# KCNFEQ_V0_1.net
KiCad netlist of a schematic drawn in Altium Designer
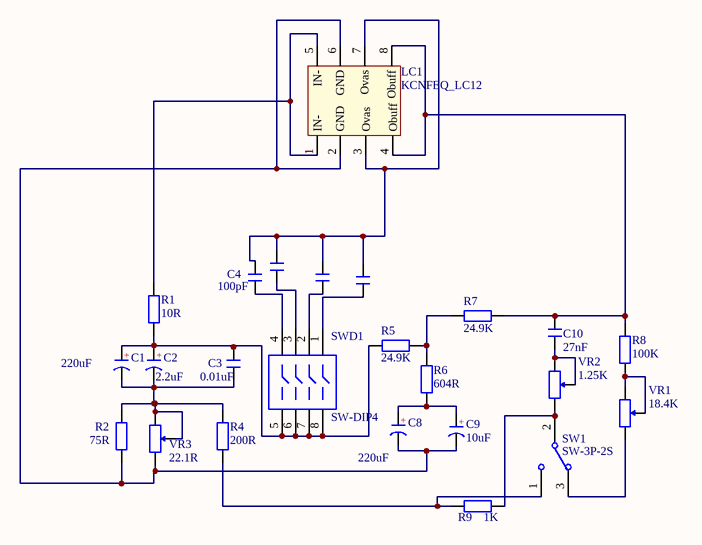
[diagram p0: KCNFEQ_V0.1.SchDoc]

(export (version "E")
  (design (tool "Eeschema 10.0.6"))
  (components
    (comp (ref "C1")
      (value "220uF")
      (footprint "CAP 5.0*10*12.5")
      (description "直插电解电容")
      (fields (field (name "版权归属") "源创客"))
      (libsource (lib "电阻-电容-电感") (part "C-CAP"))
    )
    (comp (ref "C2")
      (value "2.2uF")
      (footprint "CAP 5.0*10*12.5")
      (description "直插电解电容")
      (fields (field (name "版权归属") "源创客"))
      (libsource (lib "电阻-电容-电感") (part "C-CAP"))
    )
    (comp (ref "C3")
      (value "0.01uF")
      (footprint "CBB 6.3*6.3*5")
      (description "CBB电容")
      (fields (field (name "版权归属") "源创客"))
      (libsource (lib "电阻-电容-电感") (part "C-CBB"))
    )
    (comp (ref "C4")
      (value "100pF")
      (footprint "CBB 6.3*6.3*5")
      (description "CBB电容")
      (fields (field (name "版权归属") "源创客"))
      (libsource (lib "电阻-电容-电感") (part "C-CBB"))
    )
    (comp (ref "C6")
      (value "100pF")
      (footprint "CBB 6.3*6.3*5")
      (description "CBB电容")
      (fields (field (name "版权归属") "源创客"))
      (libsource (lib "电阻-电容-电感") (part "C-CBB"))
    )
    (comp (ref "C7")
      (value "20pF")
      (footprint "CBB 6.3*6.3*5")
      (description "CBB电容")
      (fields (field (name "版权归属") "源创客"))
      (libsource (lib "电阻-电容-电感") (part "C-CBB"))
    )
    (comp (ref "C8")
      (value "220uF")
      (footprint "CAP 5.0*10*12.5")
      (description "直插电解电容")
      (fields (field (name "版权归属") "源创客"))
      (libsource (lib "电阻-电容-电感") (part "C-CAP"))
    )
    (comp (ref "C9")
      (value "10uF")
      (footprint "CAP 5.0*10*12.5")
      (description "直插电解电容")
      (fields (field (name "版权归属") "源创客"))
      (libsource (lib "电阻-电容-电感") (part "C-CAP"))
    )
    (comp (ref "C10")
      (value "27nF")
      (footprint "CBB 6.3*6.3*5")
      (description "CBB电容")
      (fields (field (name "版权归属") "源创客"))
      (libsource (lib "电阻-电容-电感") (part "C-CBB"))
    )
    (comp (ref "C18")
      (value "60pF")
      (footprint "CBB 6.3*6.3*5")
      (description "CBB电容")
      (fields (field (name "版权归属") "源创客"))
      (libsource (lib "电阻-电容-电感") (part "C-CBB"))
    )
    (comp (ref "LC1")
      (value "KCNFEQ_LC12")
      (footprint "LC12-3.81")
      (description "King Cello Negative Feedback and EQ Board")
      (libsource (lib "KC_amp") (part "KCNFEQ_LC12"))
    )
    (comp (ref "R1")
      (value "10R")
      (footprint "RS 1/4W")
      (description "直插色环电阻")
      (fields (field (name "版权归属") "源创客"))
      (libsource (lib "电阻-电容-电感") (part "R-CRR"))
    )
    (comp (ref "R2")
      (value "75R")
      (footprint "RS 1/4W")
      (description "直插色环电阻")
      (fields (field (name "版权归属") "源创客"))
      (libsource (lib "电阻-电容-电感") (part "R-CRR"))
    )
    (comp (ref "R4")
      (value "200R")
      (footprint "RS 1/4W")
      (description "直插色环电阻")
      (fields (field (name "版权归属") "源创客"))
      (libsource (lib "电阻-电容-电感") (part "R-CRR"))
    )
    (comp (ref "R5")
      (value "24.9K")
      (footprint "RS 1/4W")
      (description "直插色环电阻")
      (fields (field (name "版权归属") "源创客"))
      (libsource (lib "电阻-电容-电感") (part "R-CRR"))
    )
    (comp (ref "R6")
      (value "604R")
      (footprint "RS 1/4W")
      (description "直插色环电阻")
      (fields (field (name "版权归属") "源创客"))
      (libsource (lib "电阻-电容-电感") (part "R-CRR"))
    )
    (comp (ref "R7")
      (value "24.9K")
      (footprint "RS 1/4W")
      (description "直插色环电阻")
      (fields (field (name "版权归属") "源创客"))
      (libsource (lib "电阻-电容-电感") (part "R-CRR"))
    )
    (comp (ref "R8")
      (value "100K")
      (footprint "RS 1/4W")
      (description "直插色环电阻")
      (fields (field (name "版权归属") "源创客"))
      (libsource (lib "电阻-电容-电感") (part "R-CRR"))
    )
    (comp (ref "R9")
      (value "1K")
      (footprint "RS 1/4W")
      (description "直插色环电阻")
      (fields (field (name "版权归属") "源创客"))
      (libsource (lib "电阻-电容-电感") (part "R-CRR"))
    )
    (comp (ref "SW1")
      (value "SW-3P-2S")
      (footprint "SS-12D06")
      (description "3 Pin 2 Switch")
      (libsource (lib "Connectors") (part "SW-3P-2S"))
    )
    (comp (ref "SWD1")
      (value "SW-DIP4")
      (footprint "DIP-8")
      (description "DIP Switch")
      (fields (field (name "PUBLISHER") "Altium Limited"))
      (libsource (lib "Miscellaneous Devices") (part "SW-DIP4"))
    )
    (comp (ref "VR1")
      (value "18.4K")
      (footprint "RS 1/2W-VR")
      (description "直插可调电阻-顶调")
      (libsource (lib "电阻-电容-电感") (part "VR-W"))
    )
    (comp (ref "VR2")
      (value "1.25K")
      (footprint "RS 1/2W-VR")
      (description "直插可调电阻-顶调")
      (libsource (lib "电阻-电容-电感") (part "VR-W"))
    )
    (comp (ref "VR3")
      (value "22.1R")
      (footprint "RS 1/2W-VR")
      (description "直插可调电阻-顶调")
      (libsource (lib "电阻-电容-电感") (part "VR-W"))
    )
  )
  (nets
    (net (code "1") (name "Net-(C1-A)") (class "Default")
      (node (ref "C1") (pin "1") (pinfunction "A_1") (pintype "passive"))
      (node (ref "C2") (pin "1") (pinfunction "A_1") (pintype "passive"))
      (node (ref "C3") (pin "1") (pinfunction "1_1") (pintype "passive"))
      (node (ref "R1") (pin "1") (pinfunction "1_1") (pintype "passive"))
      (node (ref "R5") (pin "1") (pinfunction "1_1") (pintype "passive"))
      (node (ref "SWD1") (pin "5") (pinfunction "5_5") (pintype "passive"))
      (node (ref "SWD1") (pin "6") (pinfunction "6_6") (pintype "passive"))
      (node (ref "SWD1") (pin "7") (pinfunction "7_7") (pintype "passive"))
      (node (ref "SWD1") (pin "8") (pinfunction "8_8") (pintype "passive"))
    )
    (net (code "2") (name "Net-(C1-K)") (class "Default")
      (node (ref "C1") (pin "2") (pinfunction "K_2") (pintype "passive"))
      (node (ref "C2") (pin "2") (pinfunction "K_2") (pintype "passive"))
      (node (ref "C3") (pin "2") (pinfunction "2_2") (pintype "passive"))
      (node (ref "R2") (pin "2") (pinfunction "2_2") (pintype "passive"))
      (node (ref "R4") (pin "2") (pinfunction "2_2") (pintype "passive"))
      (node (ref "VR3") (pin "1") (pinfunction "1_1") (pintype "passive"))
      (node (ref "VR3") (pin "3") (pinfunction "3_3") (pintype "passive"))
    )
    (net (code "3") (name "Net-(C4-Pad1)") (class "Default")
      (node (ref "C4") (pin "1") (pinfunction "1_1") (pintype "passive"))
      (node (ref "SWD1") (pin "4") (pinfunction "4_4") (pintype "passive"))
    )
    (net (code "4") (name "Net-(C6-Pad1)") (class "Default")
      (node (ref "C6") (pin "1") (pinfunction "1_1") (pintype "passive"))
      (node (ref "SWD1") (pin "2") (pinfunction "2_2") (pintype "passive"))
    )
    (net (code "5") (name "Net-(C7-Pad1)") (class "Default")
      (node (ref "C7") (pin "1") (pinfunction "1_1") (pintype "passive"))
      (node (ref "SWD1") (pin "1") (pinfunction "1_1") (pintype "passive"))
    )
    (net (code "6") (name "Net-(C8-A)") (class "Default")
      (node (ref "C8") (pin "1") (pinfunction "A_1") (pintype "passive"))
      (node (ref "C9") (pin "1") (pinfunction "A_1") (pintype "passive"))
      (node (ref "R6") (pin "1") (pinfunction "1_1") (pintype "passive"))
    )
    (net (code "7") (name "Net-(C8-K)") (class "Default")
      (node (ref "C8") (pin "2") (pinfunction "K_2") (pintype "passive"))
      (node (ref "C9") (pin "2") (pinfunction "K_2") (pintype "passive"))
      (node (ref "LC1") (pin "2") (pinfunction "GND_2") (pintype "passive"))
      (node (ref "LC1") (pin "6") (pinfunction "GND_6") (pintype "passive"))
      (node (ref "R2") (pin "1") (pinfunction "1_1") (pintype "passive"))
      (node (ref "VR3") (pin "2") (pinfunction "2_2") (pintype "passive"))
    )
    (net (code "8") (name "Net-(C10-Pad1)") (class "Default")
      (node (ref "C10") (pin "1") (pinfunction "1_1") (pintype "passive"))
      (node (ref "LC1") (pin "4") (pinfunction "Obuff_4") (pintype "passive"))
      (node (ref "LC1") (pin "8") (pinfunction "Obuff_8") (pintype "passive"))
      (node (ref "R7") (pin "2") (pinfunction "2_2") (pintype "passive"))
      (node (ref "R8") (pin "1") (pinfunction "1_1") (pintype "passive"))
    )
    (net (code "9") (name "Net-(C10-Pad2)") (class "Default")
      (node (ref "C10") (pin "2") (pinfunction "2_2") (pintype "passive"))
      (node (ref "VR2") (pin "1") (pinfunction "1_1") (pintype "passive"))
      (node (ref "VR2") (pin "3") (pinfunction "3_3") (pintype "passive"))
    )
    (net (code "10") (name "Net-(C18-Pad1)") (class "Default")
      (node (ref "C18") (pin "1") (pinfunction "1_1") (pintype "passive"))
      (node (ref "SWD1") (pin "3") (pinfunction "3_3") (pintype "passive"))
    )
    (net (code "11") (name "Net-(C18-Pad2)") (class "Default")
      (node (ref "C18") (pin "2") (pinfunction "2_2") (pintype "passive"))
      (node (ref "C4") (pin "2") (pinfunction "2_2") (pintype "passive"))
      (node (ref "C6") (pin "2") (pinfunction "2_2") (pintype "passive"))
      (node (ref "C7") (pin "2") (pinfunction "2_2") (pintype "passive"))
      (node (ref "LC1") (pin "3") (pinfunction "Ovas_3") (pintype "passive"))
      (node (ref "LC1") (pin "7") (pinfunction "Ovas_7") (pintype "passive"))
    )
    (net (code "12") (name "Net-(LC1-IN--Pad1)") (class "Default")
      (node (ref "LC1") (pin "1") (pinfunction "IN-_1") (pintype "passive"))
      (node (ref "LC1") (pin "5") (pinfunction "IN-_5") (pintype "passive"))
      (node (ref "R1") (pin "2") (pinfunction "2_2") (pintype "passive"))
    )
    (net (code "13") (name "Net-(R4-Pad1)") (class "Default")
      (node (ref "R4") (pin "1") (pinfunction "1_1") (pintype "passive"))
      (node (ref "R9") (pin "1") (pinfunction "1_1") (pintype "passive"))
      (node (ref "SW1") (pin "1") (pinfunction "1_1") (pintype "passive"))
    )
    (net (code "14") (name "Net-(R5-Pad2)") (class "Default")
      (node (ref "R5") (pin "2") (pinfunction "2_2") (pintype "passive"))
      (node (ref "R6") (pin "2") (pinfunction "2_2") (pintype "passive"))
      (node (ref "R7") (pin "1") (pinfunction "1_1") (pintype "passive"))
    )
    (net (code "15") (name "Net-(R8-Pad2)") (class "Default")
      (node (ref "R8") (pin "2") (pinfunction "2_2") (pintype "passive"))
      (node (ref "VR1") (pin "1") (pinfunction "1_1") (pintype "passive"))
      (node (ref "VR1") (pin "3") (pinfunction "3_3") (pintype "passive"))
    )
    (net (code "16") (name "Net-(R9-Pad2)") (class "Default")
      (node (ref "R9") (pin "2") (pinfunction "2_2") (pintype "passive"))
      (node (ref "SW1") (pin "2") (pinfunction "2_2") (pintype "passive"))
      (node (ref "VR2") (pin "2") (pinfunction "2_2") (pintype "passive"))
    )
    (net (code "17") (name "Net-(SW1-Pad3)") (class "Default")
      (node (ref "SW1") (pin "3") (pinfunction "3_3") (pintype "passive"))
      (node (ref "VR1") (pin "2") (pinfunction "2_2") (pintype "passive"))
    )
  )
)
